# war-in.net
KiCad netlist of a schematic drawn in EAGLE
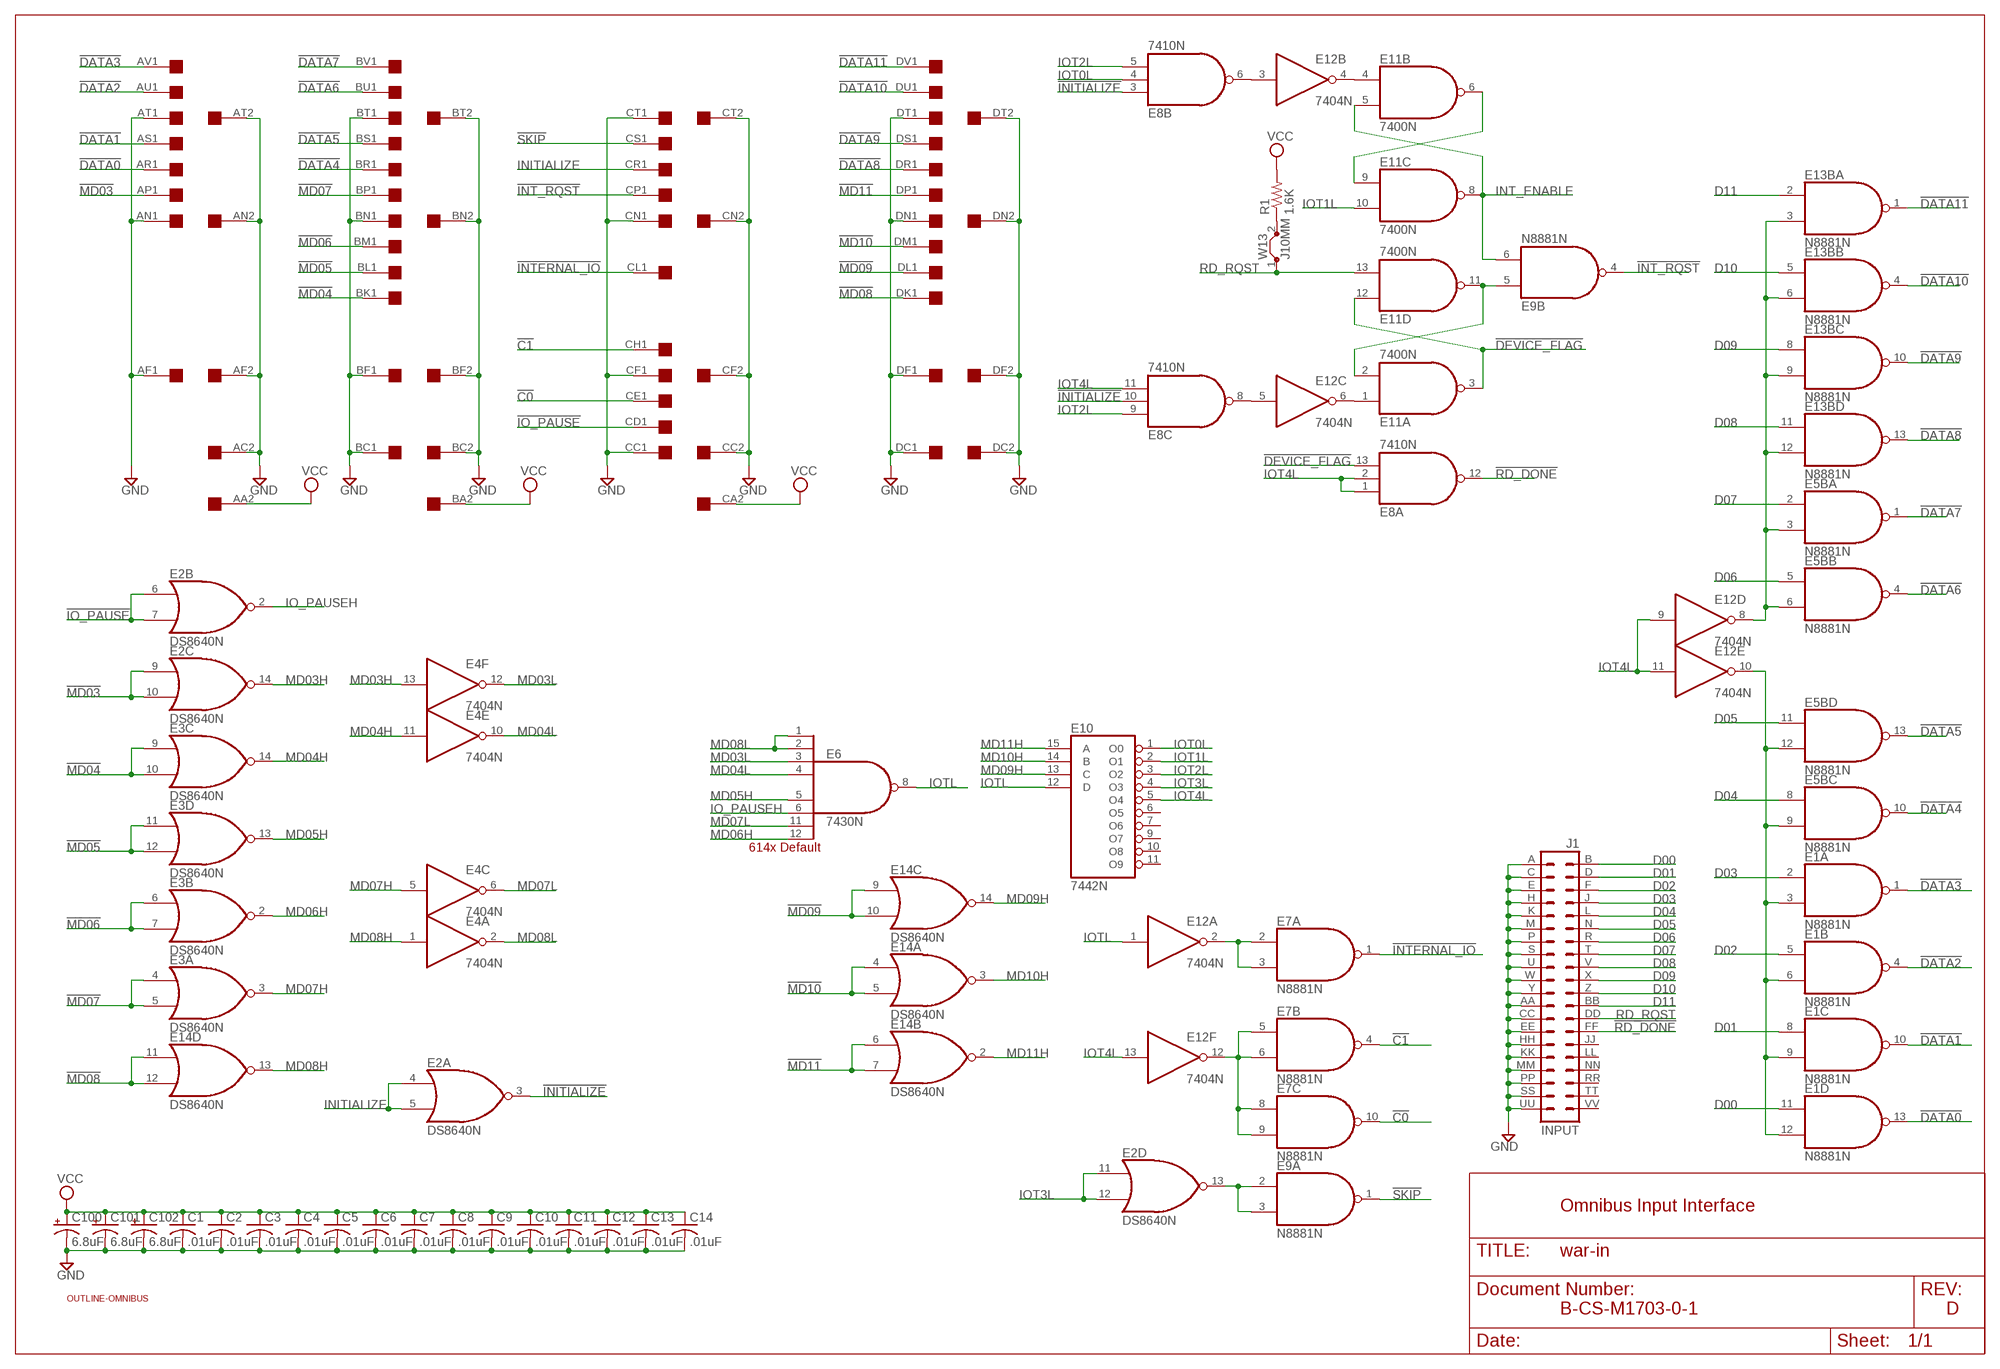
[diagram p0: schematic, sheet 1]

(export (version "E")
  (design (tool "Eeschema 10.0.6"))
  (components
    (comp (ref "C1")
      (value ".01uF")
      (footprint "eagle-import:C075-032X103")
      (libsource (lib "eagle-import") (part "C-US075-032X103"))
    )
    (comp (ref "C2")
      (value ".01uF")
      (footprint "eagle-import:C075-032X103")
      (libsource (lib "eagle-import") (part "C-US075-032X103"))
    )
    (comp (ref "C3")
      (value ".01uF")
      (footprint "eagle-import:C075-032X103")
      (libsource (lib "eagle-import") (part "C-US075-032X103"))
    )
    (comp (ref "C4")
      (value ".01uF")
      (footprint "eagle-import:C075-032X103")
      (libsource (lib "eagle-import") (part "C-US075-032X103"))
    )
    (comp (ref "C5")
      (value ".01uF")
      (footprint "eagle-import:C075-032X103")
      (libsource (lib "eagle-import") (part "C-US075-032X103"))
    )
    (comp (ref "C6")
      (value ".01uF")
      (footprint "eagle-import:C075-032X103")
      (libsource (lib "eagle-import") (part "C-US075-032X103"))
    )
    (comp (ref "C7")
      (value ".01uF")
      (footprint "eagle-import:C075-032X103")
      (libsource (lib "eagle-import") (part "C-US075-032X103"))
    )
    (comp (ref "C8")
      (value ".01uF")
      (footprint "eagle-import:C075-032X103")
      (libsource (lib "eagle-import") (part "C-US075-032X103"))
    )
    (comp (ref "C9")
      (value ".01uF")
      (footprint "eagle-import:C075-032X103")
      (libsource (lib "eagle-import") (part "C-US075-032X103"))
    )
    (comp (ref "C10")
      (value ".01uF")
      (footprint "eagle-import:C075-032X103")
      (libsource (lib "eagle-import") (part "C-US075-032X103"))
    )
    (comp (ref "C11")
      (value ".01uF")
      (footprint "eagle-import:C075-032X103")
      (libsource (lib "eagle-import") (part "C-US075-032X103"))
    )
    (comp (ref "C12")
      (value ".01uF")
      (footprint "eagle-import:C075-032X103")
      (libsource (lib "eagle-import") (part "C-US075-032X103"))
    )
    (comp (ref "C13")
      (value ".01uF")
      (footprint "eagle-import:C075-032X103")
      (libsource (lib "eagle-import") (part "C-US075-032X103"))
    )
    (comp (ref "C14")
      (value ".01uF")
      (footprint "eagle-import:C075-032X103")
      (libsource (lib "eagle-import") (part "C-US075-032X103"))
    )
    (comp (ref "C100")
      (value "6.8uF")
      (footprint "eagle-import:E12-8")
      (libsource (lib "eagle-import") (part "CPOL-USE20-8AXIAL"))
    )
    (comp (ref "C101")
      (value "6.8uF")
      (footprint "eagle-import:E12-8")
      (libsource (lib "eagle-import") (part "CPOL-USE20-8AXIAL"))
    )
    (comp (ref "C102")
      (value "6.8uF")
      (footprint "eagle-import:E12-8")
      (libsource (lib "eagle-import") (part "CPOL-USE20-8AXIAL"))
    )
    (comp (ref "E1")
      (value "N8881N")
      (footprint "eagle-import:DIL14")
      (libsource (lib "eagle-import") (part "N8881N"))
    )
    (comp (ref "E2")
      (value "DS8640N")
      (footprint "eagle-import:DIL14")
      (libsource (lib "eagle-import") (part "DS8640N"))
    )
    (comp (ref "E3")
      (value "DS8640N")
      (footprint "eagle-import:DIL14")
      (libsource (lib "eagle-import") (part "DS8640N"))
    )
    (comp (ref "E4")
      (value "7404N")
      (footprint "eagle-import:DIL14")
      (libsource (lib "eagle-import") (part "7404N"))
    )
    (comp (ref "E5B")
      (value "N8881N")
      (footprint "eagle-import:DIL14")
      (libsource (lib "eagle-import") (part "N8881N"))
    )
    (comp (ref "E6")
      (value "7430N")
      (footprint "eagle-import:DIL14")
      (libsource (lib "eagle-import") (part "7430N"))
    )
    (comp (ref "E7")
      (value "N8881N")
      (footprint "eagle-import:DIL14")
      (libsource (lib "eagle-import") (part "N8881N"))
    )
    (comp (ref "E8")
      (value "7410N")
      (footprint "eagle-import:DIL14")
      (libsource (lib "eagle-import") (part "7410N"))
    )
    (comp (ref "E9")
      (value "N8881N")
      (footprint "eagle-import:DIL14")
      (libsource (lib "eagle-import") (part "N8881N"))
    )
    (comp (ref "E10")
      (value "7442N")
      (footprint "eagle-import:DIL16")
      (libsource (lib "eagle-import") (part "7442NLS"))
    )
    (comp (ref "E11")
      (value "7400N")
      (footprint "eagle-import:DIL14")
      (libsource (lib "eagle-import") (part "7400N"))
    )
    (comp (ref "E12")
      (value "7404N")
      (footprint "eagle-import:DIL14")
      (libsource (lib "eagle-import") (part "7404N"))
    )
    (comp (ref "E13B")
      (value "N8881N")
      (footprint "eagle-import:DIL14")
      (libsource (lib "eagle-import") (part "N8881N"))
    )
    (comp (ref "E14")
      (value "DS8640N")
      (footprint "eagle-import:DIL14")
      (libsource (lib "eagle-import") (part "DS8640N"))
    )
    (comp (ref "J1")
      (value "INPUT")
      (footprint "eagle-import:DEC40PINH")
      (libsource (lib "eagle-import") (part "DEC40PINH"))
    )
    (comp (ref "R1")
      (value "1.6K")
      (footprint "eagle-import:0207_10")
      (libsource (lib "eagle-import") (part "R-US_0207/10"))
    )
    (comp (ref "U$2")
      (value "QUAD")
      (footprint "eagle-import:EDGE-CON8")
      (libsource (lib "eagle-import") (part "QUAD"))
    )
    (comp (ref "U$4")
      (value "OUTLINE-OMNIBUS")
      (footprint "eagle-import:OMNIBUS")
      (libsource (lib "eagle-import") (part "OUTLINE-OMNIBUS"))
    )
    (comp (ref "W13")
      (value "J10MM")
      (footprint "eagle-import:10")
      (libsource (lib "eagle-import") (part "J10MM"))
    )
  )
  (nets
    (net (code "1") (name "/D00") (class "Default")
      (node (ref "E1") (pin "11") (pinfunction "I0_11") (pintype "input"))
      (node (ref "J1") (pin "B") (pinfunction "2_B") (pintype "bidirectional"))
    )
    (net (code "2") (name "/D01") (class "Default")
      (node (ref "E1") (pin "8") (pinfunction "I0_8") (pintype "input"))
      (node (ref "J1") (pin "D") (pinfunction "4_D") (pintype "bidirectional"))
    )
    (net (code "3") (name "/D02") (class "Default")
      (node (ref "E1") (pin "5") (pinfunction "I0_5") (pintype "input"))
      (node (ref "J1") (pin "F") (pinfunction "6_F") (pintype "bidirectional"))
    )
    (net (code "4") (name "/D03") (class "Default")
      (node (ref "E1") (pin "2") (pinfunction "I0_2") (pintype "input"))
      (node (ref "J1") (pin "J") (pinfunction "8_J") (pintype "bidirectional"))
    )
    (net (code "5") (name "/D04") (class "Default")
      (node (ref "E5B") (pin "8") (pinfunction "I0_8") (pintype "input"))
      (node (ref "J1") (pin "L") (pinfunction "10_L") (pintype "bidirectional"))
    )
    (net (code "6") (name "/D05") (class "Default")
      (node (ref "E5B") (pin "11") (pinfunction "I0_11") (pintype "input"))
      (node (ref "J1") (pin "N") (pinfunction "12_N") (pintype "bidirectional"))
    )
    (net (code "7") (name "/D06") (class "Default")
      (node (ref "E5B") (pin "5") (pinfunction "I0_5") (pintype "input"))
      (node (ref "J1") (pin "R") (pinfunction "14_R") (pintype "bidirectional"))
    )
    (net (code "8") (name "/D07") (class "Default")
      (node (ref "E5B") (pin "2") (pinfunction "I0_2") (pintype "input"))
      (node (ref "J1") (pin "T") (pinfunction "16_T") (pintype "bidirectional"))
    )
    (net (code "9") (name "/D08") (class "Default")
      (node (ref "E13B") (pin "11") (pinfunction "I0_11") (pintype "input"))
      (node (ref "J1") (pin "V") (pinfunction "18_V") (pintype "bidirectional"))
    )
    (net (code "10") (name "/D09") (class "Default")
      (node (ref "E13B") (pin "8") (pinfunction "I0_8") (pintype "input"))
      (node (ref "J1") (pin "X") (pinfunction "20_X") (pintype "bidirectional"))
    )
    (net (code "11") (name "/D10") (class "Default")
      (node (ref "E13B") (pin "5") (pinfunction "I0_5") (pintype "input"))
      (node (ref "J1") (pin "Z") (pinfunction "22_Z") (pintype "bidirectional"))
    )
    (net (code "12") (name "/D11") (class "Default")
      (node (ref "E13B") (pin "2") (pinfunction "I0_2") (pintype "input"))
      (node (ref "J1") (pin "BB") (pinfunction "24_BB") (pintype "bidirectional"))
    )
    (net (code "13") (name "/INITIALIZE") (class "Default")
      (node (ref "E2") (pin "4") (pinfunction "I0_4") (pintype "input"))
      (node (ref "E2") (pin "5") (pinfunction "I1_5") (pintype "input"))
      (node (ref "U$2") (pin "CR1") (pinfunction "1_CR1") (pintype "bidirectional"))
    )
    (net (code "14") (name "/INT_ENABLE") (class "Default")
      (node (ref "E11") (pin "5") (pinfunction "I1_5") (pintype "input"))
      (node (ref "E11") (pin "8") (pinfunction "O_8") (pintype "output"))
      (node (ref "E9") (pin "6") (pinfunction "I1_6") (pintype "input"))
    )
    (net (code "15") (name "/IOT0L") (class "Default")
      (node (ref "E10") (pin "1") (pinfunction "O0_1") (pintype "output"))
      (node (ref "E8") (pin "4") (pinfunction "I1_4") (pintype "input"))
    )
    (net (code "16") (name "/IOT1L") (class "Default")
      (node (ref "E10") (pin "2") (pinfunction "O1_2") (pintype "output"))
      (node (ref "E11") (pin "10") (pinfunction "I1_10") (pintype "input"))
    )
    (net (code "17") (name "/IOT2L") (class "Default")
      (node (ref "E10") (pin "3") (pinfunction "O2_3") (pintype "output"))
      (node (ref "E8") (pin "5") (pinfunction "I2_5") (pintype "input"))
      (node (ref "E8") (pin "9") (pinfunction "I0_9") (pintype "input"))
    )
    (net (code "18") (name "/IOT3L") (class "Default")
      (node (ref "E10") (pin "4") (pinfunction "O3_4") (pintype "output"))
      (node (ref "E2") (pin "11") (pinfunction "I0_11") (pintype "input"))
      (node (ref "E2") (pin "12") (pinfunction "I1_12") (pintype "input"))
    )
    (net (code "19") (name "/IOT4L") (class "Default")
      (node (ref "E10") (pin "5") (pinfunction "O4_5") (pintype "output"))
      (node (ref "E12") (pin "11") (pinfunction "I_11") (pintype "input"))
      (node (ref "E12") (pin "13") (pinfunction "I_13") (pintype "input"))
      (node (ref "E12") (pin "9") (pinfunction "I_9") (pintype "input"))
      (node (ref "E8") (pin "1") (pinfunction "I0_1") (pintype "input"))
      (node (ref "E8") (pin "11") (pinfunction "I2_11") (pintype "input"))
      (node (ref "E8") (pin "2") (pinfunction "I1_2") (pintype "input"))
    )
    (net (code "20") (name "/IOTL") (class "Default")
      (node (ref "E10") (pin "12") (pinfunction "D_12") (pintype "input"))
      (node (ref "E12") (pin "1") (pinfunction "I_1") (pintype "input"))
      (node (ref "E6") (pin "8") (pinfunction "O_8") (pintype "output"))
    )
    (net (code "21") (name "/IO_PAUSEH") (class "Default")
      (node (ref "E2") (pin "2") (pinfunction "O_2") (pintype "output"))
      (node (ref "E6") (pin "6") (pinfunction "I5_6") (pintype "input"))
    )
    (net (code "22") (name "/MD03H") (class "Default")
      (node (ref "E2") (pin "14") (pinfunction "O_14") (pintype "output"))
      (node (ref "E4") (pin "13") (pinfunction "I_13") (pintype "input"))
    )
    (net (code "23") (name "/MD03L") (class "Default")
      (node (ref "E4") (pin "12") (pinfunction "O_12") (pintype "output"))
      (node (ref "E6") (pin "3") (pinfunction "I2_3") (pintype "input"))
    )
    (net (code "24") (name "/MD04H") (class "Default")
      (node (ref "E3") (pin "14") (pinfunction "O_14") (pintype "output"))
      (node (ref "E4") (pin "11") (pinfunction "I_11") (pintype "input"))
    )
    (net (code "25") (name "/MD04L") (class "Default")
      (node (ref "E4") (pin "10") (pinfunction "O_10") (pintype "output"))
      (node (ref "E6") (pin "4") (pinfunction "I3_4") (pintype "input"))
    )
    (net (code "26") (name "/MD05H") (class "Default")
      (node (ref "E3") (pin "13") (pinfunction "O_13") (pintype "output"))
      (node (ref "E6") (pin "5") (pinfunction "I4_5") (pintype "input"))
    )
    (net (code "27") (name "/MD06H") (class "Default")
      (node (ref "E3") (pin "2") (pinfunction "O_2") (pintype "output"))
      (node (ref "E6") (pin "12") (pinfunction "I7_12") (pintype "input"))
    )
    (net (code "28") (name "/MD07H") (class "Default")
      (node (ref "E3") (pin "3") (pinfunction "O_3") (pintype "output"))
      (node (ref "E4") (pin "5") (pinfunction "I_5") (pintype "input"))
    )
    (net (code "29") (name "/MD07L") (class "Default")
      (node (ref "E4") (pin "6") (pinfunction "O_6") (pintype "output"))
      (node (ref "E6") (pin "11") (pinfunction "I6_11") (pintype "input"))
    )
    (net (code "30") (name "/MD08H") (class "Default")
      (node (ref "E14") (pin "13") (pinfunction "O_13") (pintype "output"))
      (node (ref "E4") (pin "1") (pinfunction "I_1") (pintype "input"))
    )
    (net (code "31") (name "/MD08L") (class "Default")
      (node (ref "E4") (pin "2") (pinfunction "O_2") (pintype "output"))
      (node (ref "E6") (pin "1") (pinfunction "I0_1") (pintype "input"))
      (node (ref "E6") (pin "2") (pinfunction "I1_2") (pintype "input"))
    )
    (net (code "32") (name "/MD09H") (class "Default")
      (node (ref "E10") (pin "13") (pinfunction "C_13") (pintype "input"))
      (node (ref "E14") (pin "14") (pinfunction "O_14") (pintype "output"))
    )
    (net (code "33") (name "/MD10H") (class "Default")
      (node (ref "E10") (pin "14") (pinfunction "B_14") (pintype "input"))
      (node (ref "E14") (pin "3") (pinfunction "O_3") (pintype "output"))
    )
    (net (code "34") (name "/MD11H") (class "Default")
      (node (ref "E10") (pin "15") (pinfunction "A_15") (pintype "input"))
      (node (ref "E14") (pin "2") (pinfunction "O_2") (pintype "output"))
    )
    (net (code "35") (name "/RD_RQST") (class "Default")
      (node (ref "E11") (pin "13") (pinfunction "I1_13") (pintype "input"))
      (node (ref "J1") (pin "DD") (pinfunction "26_DD") (pintype "bidirectional"))
      (node (ref "W13") (pin "1") (pinfunction "1_1") (pintype "passive"))
    )
    (net (code "36") (name "/~{C0}") (class "Default")
      (node (ref "E7") (pin "10") (pinfunction "O_10") (pintype "open_collector"))
      (node (ref "U$2") (pin "CE1") (pinfunction "1_CE1") (pintype "bidirectional"))
    )
    (net (code "37") (name "/~{C1}") (class "Default")
      (node (ref "E7") (pin "4") (pinfunction "O_4") (pintype "open_collector"))
      (node (ref "U$2") (pin "CH1") (pinfunction "1_CH1") (pintype "bidirectional"))
    )
    (net (code "38") (name "/~{DATA0}") (class "Default")
      (node (ref "E1") (pin "13") (pinfunction "O_13") (pintype "open_collector"))
      (node (ref "U$2") (pin "AR1") (pinfunction "1_AR1") (pintype "bidirectional"))
    )
    (net (code "39") (name "/~{DATA1}") (class "Default")
      (node (ref "E1") (pin "10") (pinfunction "O_10") (pintype "open_collector"))
      (node (ref "U$2") (pin "AS1") (pinfunction "1_AS1") (pintype "bidirectional"))
    )
    (net (code "40") (name "/~{DATA2}") (class "Default")
      (node (ref "E1") (pin "4") (pinfunction "O_4") (pintype "open_collector"))
      (node (ref "U$2") (pin "AU1") (pinfunction "1_AU1") (pintype "bidirectional"))
    )
    (net (code "41") (name "/~{DATA3}") (class "Default")
      (node (ref "E1") (pin "1") (pinfunction "O_1") (pintype "open_collector"))
      (node (ref "U$2") (pin "AV1") (pinfunction "1_AV1") (pintype "bidirectional"))
    )
    (net (code "42") (name "/~{DATA4}") (class "Default")
      (node (ref "E5B") (pin "10") (pinfunction "O_10") (pintype "open_collector"))
      (node (ref "U$2") (pin "BR1") (pinfunction "1_BR1") (pintype "bidirectional"))
    )
    (net (code "43") (name "/~{DATA5}") (class "Default")
      (node (ref "E5B") (pin "13") (pinfunction "O_13") (pintype "open_collector"))
      (node (ref "U$2") (pin "BS1") (pinfunction "1_BS1") (pintype "bidirectional"))
    )
    (net (code "44") (name "/~{DATA6}") (class "Default")
      (node (ref "E5B") (pin "4") (pinfunction "O_4") (pintype "open_collector"))
      (node (ref "U$2") (pin "BU1") (pinfunction "1_BU1") (pintype "bidirectional"))
    )
    (net (code "45") (name "/~{DATA7}") (class "Default")
      (node (ref "E5B") (pin "1") (pinfunction "O_1") (pintype "open_collector"))
      (node (ref "U$2") (pin "BV1") (pinfunction "1_BV1") (pintype "bidirectional"))
    )
    (net (code "46") (name "/~{DATA8}") (class "Default")
      (node (ref "E13B") (pin "13") (pinfunction "O_13") (pintype "open_collector"))
      (node (ref "U$2") (pin "DR1") (pinfunction "1_DR1") (pintype "bidirectional"))
    )
    (net (code "47") (name "/~{DATA9}") (class "Default")
      (node (ref "E13B") (pin "10") (pinfunction "O_10") (pintype "open_collector"))
      (node (ref "U$2") (pin "DS1") (pinfunction "1_DS1") (pintype "bidirectional"))
    )
    (net (code "48") (name "/~{DATA10}") (class "Default")
      (node (ref "E13B") (pin "4") (pinfunction "O_4") (pintype "open_collector"))
      (node (ref "U$2") (pin "DU1") (pinfunction "1_DU1") (pintype "bidirectional"))
    )
    (net (code "49") (name "/~{DATA11}") (class "Default")
      (node (ref "E13B") (pin "1") (pinfunction "O_1") (pintype "open_collector"))
      (node (ref "U$2") (pin "DV1") (pinfunction "1_DV1") (pintype "bidirectional"))
    )
    (net (code "50") (name "/~{DEVICE_FLAG}") (class "Default")
      (node (ref "E11") (pin "12") (pinfunction "I0_12") (pintype "input"))
      (node (ref "E11") (pin "3") (pinfunction "O_3") (pintype "output"))
      (node (ref "E8") (pin "13") (pinfunction "I2_13") (pintype "input"))
    )
    (net (code "51") (name "/~{INITIALIZE}") (class "Default")
      (node (ref "E2") (pin "3") (pinfunction "O_3") (pintype "output"))
      (node (ref "E8") (pin "10") (pinfunction "I1_10") (pintype "input"))
      (node (ref "E8") (pin "3") (pinfunction "I0_3") (pintype "input"))
    )
    (net (code "52") (name "/~{INTERNAL_IO}") (class "Default")
      (node (ref "E7") (pin "1") (pinfunction "O_1") (pintype "open_collector"))
      (node (ref "U$2") (pin "CL1") (pinfunction "1_CL1") (pintype "bidirectional"))
    )
    (net (code "53") (name "/~{INT_RQST}") (class "Default")
      (node (ref "E9") (pin "4") (pinfunction "O_4") (pintype "open_collector"))
      (node (ref "U$2") (pin "CP1") (pinfunction "1_CP1") (pintype "bidirectional"))
    )
    (net (code "54") (name "/~{IO_PAUSE}") (class "Default")
      (node (ref "E2") (pin "6") (pinfunction "I0_6") (pintype "input"))
      (node (ref "E2") (pin "7") (pinfunction "I1_7") (pintype "input"))
      (node (ref "U$2") (pin "CD1") (pinfunction "1_CD1") (pintype "bidirectional"))
    )
    (net (code "55") (name "/~{MD03}") (class "Default")
      (node (ref "E2") (pin "10") (pinfunction "I1_10") (pintype "input"))
      (node (ref "E2") (pin "9") (pinfunction "I0_9") (pintype "input"))
      (node (ref "U$2") (pin "AP1") (pinfunction "1_AP1") (pintype "bidirectional"))
    )
    (net (code "56") (name "/~{MD04}") (class "Default")
      (node (ref "E3") (pin "10") (pinfunction "I1_10") (pintype "input"))
      (node (ref "E3") (pin "9") (pinfunction "I0_9") (pintype "input"))
      (node (ref "U$2") (pin "BK1") (pinfunction "1_BK1") (pintype "bidirectional"))
    )
    (net (code "57") (name "/~{MD05}") (class "Default")
      (node (ref "E3") (pin "11") (pinfunction "I0_11") (pintype "input"))
      (node (ref "E3") (pin "12") (pinfunction "I1_12") (pintype "input"))
      (node (ref "U$2") (pin "BL1") (pinfunction "1_BL1") (pintype "bidirectional"))
    )
    (net (code "58") (name "/~{MD06}") (class "Default")
      (node (ref "E3") (pin "6") (pinfunction "I0_6") (pintype "input"))
      (node (ref "E3") (pin "7") (pinfunction "I1_7") (pintype "input"))
      (node (ref "U$2") (pin "BM1") (pinfunction "1_BM1") (pintype "bidirectional"))
    )
    (net (code "59") (name "/~{MD07}") (class "Default")
      (node (ref "E3") (pin "4") (pinfunction "I0_4") (pintype "input"))
      (node (ref "E3") (pin "5") (pinfunction "I1_5") (pintype "input"))
      (node (ref "U$2") (pin "BP1") (pinfunction "1_BP1") (pintype "bidirectional"))
    )
    (net (code "60") (name "/~{MD08}") (class "Default")
      (node (ref "E14") (pin "11") (pinfunction "I0_11") (pintype "input"))
      (node (ref "E14") (pin "12") (pinfunction "I1_12") (pintype "input"))
      (node (ref "U$2") (pin "DK1") (pinfunction "1_DK1") (pintype "bidirectional"))
    )
    (net (code "61") (name "/~{MD09}") (class "Default")
      (node (ref "E14") (pin "10") (pinfunction "I1_10") (pintype "input"))
      (node (ref "E14") (pin "9") (pinfunction "I0_9") (pintype "input"))
      (node (ref "U$2") (pin "DL1") (pinfunction "1_DL1") (pintype "bidirectional"))
    )
    (net (code "62") (name "/~{MD10}") (class "Default")
      (node (ref "E14") (pin "4") (pinfunction "I0_4") (pintype "input"))
      (node (ref "E14") (pin "5") (pinfunction "I1_5") (pintype "input"))
      (node (ref "U$2") (pin "DM1") (pinfunction "1_DM1") (pintype "bidirectional"))
    )
    (net (code "63") (name "/~{MD11}") (class "Default")
      (node (ref "E14") (pin "6") (pinfunction "I0_6") (pintype "input"))
      (node (ref "E14") (pin "7") (pinfunction "I1_7") (pintype "input"))
      (node (ref "U$2") (pin "DP1") (pinfunction "1_DP1") (pintype "bidirectional"))
    )
    (net (code "64") (name "/~{RD_DONE}") (class "Default")
      (node (ref "E8") (pin "12") (pinfunction "O_12") (pintype "output"))
      (node (ref "J1") (pin "FF") (pinfunction "28_FF") (pintype "bidirectional"))
    )
    (net (code "65") (name "/~{SKIP}") (class "Default")
      (node (ref "E9") (pin "1") (pinfunction "O_1") (pintype "open_collector"))
      (node (ref "U$2") (pin "CS1") (pinfunction "1_CS1") (pintype "bidirectional"))
    )
    (net (code "66") (name "GND") (class "Default")
      (node (ref "C1") (pin "2") (pinfunction "2_2") (pintype "passive"))
      (node (ref "C10") (pin "2") (pinfunction "2_2") (pintype "passive"))
      (node (ref "C100") (pin "-") (pinfunction "-_-") (pintype "passive"))
      (node (ref "C101") (pin "-") (pinfunction "-_-") (pintype "passive"))
      (node (ref "C102") (pin "-") (pinfunction "-_-") (pintype "passive"))
      (node (ref "C11") (pin "2") (pinfunction "2_2") (pintype "passive"))
      (node (ref "C12") (pin "2") (pinfunction "2_2") (pintype "passive"))
      (node (ref "C13") (pin "2") (pinfunction "2_2") (pintype "passive"))
      (node (ref "C14") (pin "2") (pinfunction "2_2") (pintype "passive"))
      (node (ref "C2") (pin "2") (pinfunction "2_2") (pintype "passive"))
      (node (ref "C3") (pin "2") (pinfunction "2_2") (pintype "passive"))
      (node (ref "C4") (pin "2") (pinfunction "2_2") (pintype "passive"))
      (node (ref "C5") (pin "2") (pinfunction "2_2") (pintype "passive"))
      (node (ref "C6") (pin "2") (pinfunction "2_2") (pintype "passive"))
      (node (ref "C7") (pin "2") (pinfunction "2_2") (pintype "passive"))
      (node (ref "C8") (pin "2") (pinfunction "2_2") (pintype "passive"))
      (node (ref "C9") (pin "2") (pinfunction "2_2") (pintype "passive"))
      (node (ref "J1") (pin "A") (pinfunction "1_A") (pintype "bidirectional"))
      (node (ref "J1") (pin "AA") (pinfunction "23_AA") (pintype "bidirectional"))
      (node (ref "J1") (pin "C") (pinfunction "3_C") (pintype "bidirectional"))
      (node (ref "J1") (pin "CC") (pinfunction "25_CC") (pintype "bidirectional"))
      (node (ref "J1") (pin "E") (pinfunction "5_E") (pintype "bidirectional"))
      (node (ref "J1") (pin "EE") (pinfunction "27_EE") (pintype "bidirectional"))
      (node (ref "J1") (pin "H") (pinfunction "7_H") (pintype "bidirectional"))
      (node (ref "J1") (pin "HH") (pinfunction "29_HH") (pintype "bidirectional"))
      (node (ref "J1") (pin "K") (pinfunction "9_K") (pintype "bidirectional"))
      (node (ref "J1") (pin "KK") (pinfunction "31_KK") (pintype "bidirectional"))
      (node (ref "J1") (pin "M") (pinfunction "11_M") (pintype "bidirectional"))
      (node (ref "J1") (pin "MM") (pinfunction "33_MM") (pintype "bidirectional"))
      (node (ref "J1") (pin "P") (pinfunction "13_P") (pintype "bidirectional"))
      (node (ref "J1") (pin "PP") (pinfunction "35_PP") (pintype "bidirectional"))
      (node (ref "J1") (pin "S") (pinfunction "15_S") (pintype "bidirectional"))
      (node (ref "J1") (pin "SS") (pinfunction "37_SS") (pintype "bidirectional"))
      (node (ref "J1") (pin "U") (pinfunction "17_U") (pintype "bidirectional"))
      (node (ref "J1") (pin "UU") (pinfunction "39_UU") (pintype "bidirectional"))
      (node (ref "J1") (pin "W") (pinfunction "19_W") (pintype "bidirectional"))
      (node (ref "J1") (pin "Y") (pinfunction "21_Y") (pintype "bidirectional"))
      (node (ref "U$2") (pin "AC2") (pinfunction "1_AC2") (pintype "bidirectional"))
      (node (ref "U$2") (pin "AF1") (pinfunction "1_AF1") (pintype "bidirectional"))
      (node (ref "U$2") (pin "AF2") (pinfunction "1_AF2") (pintype "bidirectional"))
      (node (ref "U$2") (pin "AN1") (pinfunction "1_AN1") (pintype "bidirectional"))
      (node (ref "U$2") (pin "AN2") (pinfunction "1_AN2") (pintype "bidirectional"))
      (node (ref "U$2") (pin "AT1") (pinfunction "1_AT1") (pintype "bidirectional"))
      (node (ref "U$2") (pin "AT2") (pinfunction "1_AT2") (pintype "bidirectional"))
      (node (ref "U$2") (pin "BC1") (pinfunction "1_BC1") (pintype "bidirectional"))
      (node (ref "U$2") (pin "BC2") (pinfunction "1_BC2") (pintype "bidirectional"))
      (node (ref "U$2") (pin "BF1") (pinfunction "1_BF1") (pintype "bidirectional"))
      (node (ref "U$2") (pin "BF2") (pinfunction "1_BF2") (pintype "bidirectional"))
      (node (ref "U$2") (pin "BN1") (pinfunction "1_BN1") (pintype "bidirectional"))
      (node (ref "U$2") (pin "BN2") (pinfunction "1_BN2") (pintype "bidirectional"))
      (node (ref "U$2") (pin "BT1") (pinfunction "1_BT1") (pintype "bidirectional"))
      (node (ref "U$2") (pin "BT2") (pinfunction "1_BT2") (pintype "bidirectional"))
      (node (ref "U$2") (pin "CC1") (pinfunction "1_CC1") (pintype "bidirectional"))
      (node (ref "U$2") (pin "CC2") (pinfunction "1_CC2") (pintype "bidirectional"))
      (node (ref "U$2") (pin "CF1") (pinfunction "1_CF1") (pintype "bidirectional"))
      (node (ref "U$2") (pin "CF2") (pinfunction "1_CF2") (pintype "bidirectional"))
      (node (ref "U$2") (pin "CN1") (pinfunction "1_CN1") (pintype "bidirectional"))
      (node (ref "U$2") (pin "CN2") (pinfunction "1_CN2") (pintype "bidirectional"))
      (node (ref "U$2") (pin "CT1") (pinfunction "1_CT1") (pintype "bidirectional"))
      (node (ref "U$2") (pin "CT2") (pinfunction "1_CT2") (pintype "bidirectional"))
      (node (ref "U$2") (pin "DC1") (pinfunction "1_DC1") (pintype "bidirectional"))
      (node (ref "U$2") (pin "DC2") (pinfunction "1_DC2") (pintype "bidirectional"))
      (node (ref "U$2") (pin "DF1") (pinfunction "1_DF1") (pintype "bidirectional"))
      (node (ref "U$2") (pin "DF2") (pinfunction "1_DF2") (pintype "bidirectional"))
      (node (ref "U$2") (pin "DN1") (pinfunction "1_DN1") (pintype "bidirectional"))
      (node (ref "U$2") (pin "DN2") (pinfunction "1_DN2") (pintype "bidirectional"))
      (node (ref "U$2") (pin "DT1") (pinfunction "1_DT1") (pintype "bidirectional"))
      (node (ref "U$2") (pin "DT2") (pinfunction "1_DT2") (pintype "bidirectional"))
    )
    (net (code "67") (name "Net-(E2D-O)") (class "Default")
      (node (ref "E2") (pin "13") (pinfunction "O_13") (pintype "output"))
      (node (ref "E9") (pin "2") (pinfunction "I0_2") (pintype "input"))
      (node (ref "E9") (pin "3") (pinfunction "I1_3") (pintype "input"))
    )
    (net (code "68") (name "Net-(E11A-I0)") (class "Default")
      (node (ref "E11") (pin "1") (pinfunction "I0_1") (pintype "input"))
      (node (ref "E12") (pin "6") (pinfunction "O_6") (pintype "output"))
    )
    (net (code "69") (name "Net-(E11A-I1)") (class "Default")
      (node (ref "E11") (pin "11") (pinfunction "O_11") (pintype "output"))
      (node (ref "E11") (pin "2") (pinfunction "I1_2") (pintype "input"))
      (node (ref "E9") (pin "5") (pinfunction "I0_5") (pintype "input"))
    )
    (net (code "70") (name "Net-(E11B-I0)") (class "Default")
      (node (ref "E11") (pin "4") (pinfunction "I0_4") (pintype "input"))
      (node (ref "E12") (pin "4") (pinfunction "O_4") (pintype "output"))
    )
    (net (code "71") (name "Net-(E11B-O)") (class "Default")
      (node (ref "E11") (pin "6") (pinfunction "O_6") (pintype "output"))
      (node (ref "E11") (pin "9") (pinfunction "I0_9") (pintype "input"))
    )
    (net (code "72") (name "Net-(E12A-O)") (class "Default")
      (node (ref "E12") (pin "2") (pinfunction "O_2") (pintype "output"))
      (node (ref "E7") (pin "2") (pinfunction "I0_2") (pintype "input"))
      (node (ref "E7") (pin "3") (pinfunction "I1_3") (pintype "input"))
    )
    (net (code "73") (name "Net-(E12B-I)") (class "Default")
      (node (ref "E12") (pin "3") (pinfunction "I_3") (pintype "input"))
      (node (ref "E8") (pin "6") (pinfunction "O_6") (pintype "output"))
    )
    (net (code "74") (name "Net-(E12C-I)") (class "Default")
      (node (ref "E12") (pin "5") (pinfunction "I_5") (pintype "input"))
      (node (ref "E8") (pin "8") (pinfunction "O_8") (pintype "output"))
    )
    (net (code "75") (name "Net-(E12D-O)") (class "Default")
      (node (ref "E12") (pin "8") (pinfunction "O_8") (pintype "output"))
      (node (ref "E13B") (pin "12") (pinfunction "I1_12") (pintype "input"))
      (node (ref "E13B") (pin "3") (pinfunction "I1_3") (pintype "input"))
      (node (ref "E13B") (pin "6") (pinfunction "I1_6") (pintype "input"))
      (node (ref "E13B") (pin "9") (pinfunction "I1_9") (pintype "input"))
      (node (ref "E5B") (pin "3") (pinfunction "I1_3") (pintype "input"))
      (node (ref "E5B") (pin "6") (pinfunction "I1_6") (pintype "input"))
    )
    (net (code "76") (name "Net-(E12E-O)") (class "Default")
      (node (ref "E1") (pin "12") (pinfunction "I1_12") (pintype "input"))
      (node (ref "E1") (pin "3") (pinfunction "I1_3") (pintype "input"))
      (node (ref "E1") (pin "6") (pinfunction "I1_6") (pintype "input"))
      (node (ref "E1") (pin "9") (pinfunction "I1_9") (pintype "input"))
      (node (ref "E12") (pin "10") (pinfunction "O_10") (pintype "output"))
      (node (ref "E5B") (pin "12") (pinfunction "I1_12") (pintype "input"))
      (node (ref "E5B") (pin "9") (pinfunction "I1_9") (pintype "input"))
    )
    (net (code "77") (name "Net-(E12F-O)") (class "Default")
      (node (ref "E12") (pin "12") (pinfunction "O_12") (pintype "output"))
      (node (ref "E7") (pin "5") (pinfunction "I0_5") (pintype "input"))
      (node (ref "E7") (pin "6") (pinfunction "I1_6") (pintype "input"))
      (node (ref "E7") (pin "8") (pinfunction "I0_8") (pintype "input"))
      (node (ref "E7") (pin "9") (pinfunction "I1_9") (pintype "input"))
    )
    (net (code "78") (name "Net-(R1-Pad1)") (class "Default")
      (node (ref "R1") (pin "1") (pinfunction "1_1") (pintype "passive"))
      (node (ref "W13") (pin "2") (pinfunction "2_2") (pintype "passive"))
    )
    (net (code "79") (name "VCC") (class "Default")
      (node (ref "C1") (pin "1") (pinfunction "1_1") (pintype "passive"))
      (node (ref "C10") (pin "1") (pinfunction "1_1") (pintype "passive"))
      (node (ref "C100") (pin "+") (pinfunction "+_+") (pintype "passive"))
      (node (ref "C101") (pin "+") (pinfunction "+_+") (pintype "passive"))
      (node (ref "C102") (pin "+") (pinfunction "+_+") (pintype "passive"))
      (node (ref "C11") (pin "1") (pinfunction "1_1") (pintype "passive"))
      (node (ref "C12") (pin "1") (pinfunction "1_1") (pintype "passive"))
      (node (ref "C13") (pin "1") (pinfunction "1_1") (pintype "passive"))
      (node (ref "C14") (pin "1") (pinfunction "1_1") (pintype "passive"))
      (node (ref "C2") (pin "1") (pinfunction "1_1") (pintype "passive"))
      (node (ref "C3") (pin "1") (pinfunction "1_1") (pintype "passive"))
      (node (ref "C4") (pin "1") (pinfunction "1_1") (pintype "passive"))
      (node (ref "C5") (pin "1") (pinfunction "1_1") (pintype "passive"))
      (node (ref "C6") (pin "1") (pinfunction "1_1") (pintype "passive"))
      (node (ref "C7") (pin "1") (pinfunction "1_1") (pintype "passive"))
      (node (ref "C8") (pin "1") (pinfunction "1_1") (pintype "passive"))
      (node (ref "C9") (pin "1") (pinfunction "1_1") (pintype "passive"))
      (node (ref "R1") (pin "2") (pinfunction "2_2") (pintype "passive"))
      (node (ref "U$2") (pin "AA2") (pinfunction "1_AA2") (pintype "bidirectional"))
      (node (ref "U$2") (pin "BA2") (pinfunction "1_BA2") (pintype "bidirectional"))
      (node (ref "U$2") (pin "CA2") (pinfunction "1_CA2") (pintype "bidirectional"))
    )
    (net (code "80") (name "unconnected-(E10A-O5-Pad6)") (class "Default")
      (node (ref "E10") (pin "6") (pinfunction "O5_6") (pintype "output"))
    )
    (net (code "81") (name "unconnected-(E10A-O6-Pad7)") (class "Default")
      (node (ref "E10") (pin "7") (pinfunction "O6_7") (pintype "output"))
    )
    (net (code "82") (name "unconnected-(E10A-O7-Pad9)") (class "Default")
      (node (ref "E10") (pin "9") (pinfunction "O7_9") (pintype "output"))
    )
    (net (code "83") (name "unconnected-(E10A-O8-Pad10)") (class "Default")
      (node (ref "E10") (pin "10") (pinfunction "O8_10") (pintype "output"))
    )
    (net (code "84") (name "unconnected-(E10A-O9-Pad11)") (class "Default")
      (node (ref "E10") (pin "11") (pinfunction "O9_11") (pintype "output"))
    )
    (net (code "85") (name "unconnected-(J1-30-PadJJ)") (class "Default")
      (node (ref "J1") (pin "JJ") (pinfunction "30_JJ") (pintype "bidirectional"))
    )
    (net (code "86") (name "unconnected-(J1-32-PadLL)") (class "Default")
      (node (ref "J1") (pin "LL") (pinfunction "32_LL") (pintype "bidirectional"))
    )
    (net (code "87") (name "unconnected-(J1-34-PadNN)") (class "Default")
      (node (ref "J1") (pin "NN") (pinfunction "34_NN") (pintype "bidirectional"))
    )
    (net (code "88") (name "unconnected-(J1-36-PadRR)") (class "Default")
      (node (ref "J1") (pin "RR") (pinfunction "36_RR") (pintype "bidirectional"))
    )
    (net (code "89") (name "unconnected-(J1-38-PadTT)") (class "Default")
      (node (ref "J1") (pin "TT") (pinfunction "38_TT") (pintype "bidirectional"))
    )
    (net (code "90") (name "unconnected-(J1-40-PadVV)") (class "Default")
      (node (ref "J1") (pin "VV") (pinfunction "40_VV") (pintype "bidirectional"))
    )
  )
)
